# SWR_Tandem_Match.net
KiCad netlist of a schematic drawn in Altium Designer
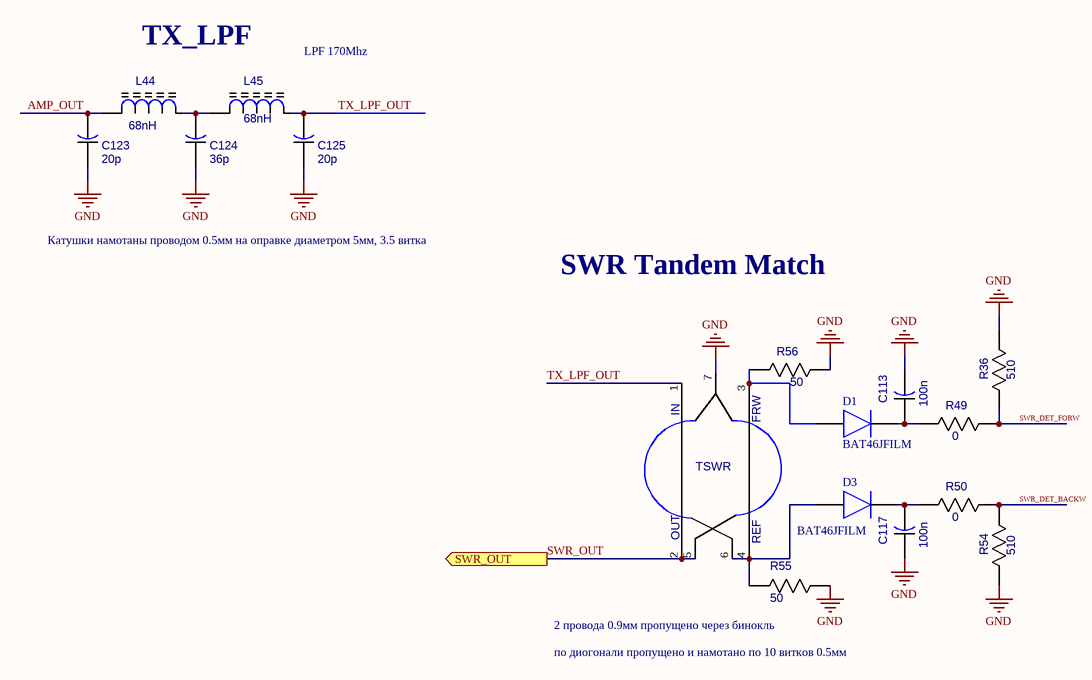
[diagram p0: SWR Tandem Match.SchDoc]

(export (version "E")
  (design (tool "Eeschema 10.0.6"))
  (components
    (comp (ref "C113")
      (value "100n")
      (footprint "CAP_0805")
      (description "CAP_0805")
      (libsource (lib "*") (part "CAP_0805"))
    )
    (comp (ref "C117")
      (value "100n")
      (footprint "CAP_0805")
      (description "CAP_0805")
      (libsource (lib "*") (part "CAP_0805"))
    )
    (comp (ref "C123")
      (value "20p")
      (footprint "CAP_1206")
      (description "CAP_1206")
      (libsource (lib "*") (part "CAP_1206"))
    )
    (comp (ref "C124")
      (value "36p")
      (footprint "CAP_1206")
      (description "CAP_1206")
      (libsource (lib "*") (part "CAP_1206"))
    )
    (comp (ref "C125")
      (value "20p")
      (footprint "CAP_1206")
      (description "CAP_1206")
      (libsource (lib "*") (part "CAP_1206"))
    )
    (comp (ref "D1")
      (value "BAT46JFILM")
      (footprint "SamacSys:SOD2513X117N")
      (description "Diode")
      (fields (field (name "MOUSER PART NUMBER") "511-BAT46JFILM") (field (name "RS PART NUMBER") "7146847P"))
      (libsource (lib "*") (part "BAT46JFILM"))
    )
    (comp (ref "D3")
      (value "BAT46JFILM")
      (footprint "SamacSys:SOD2513X117N")
      (description "Diode")
      (fields (field (name "MOUSER PART NUMBER") "511-BAT46JFILM") (field (name "RS PART NUMBER") "7146847P"))
      (libsource (lib "*") (part "BAT46JFILM"))
    )
    (comp (ref "L44")
      (value "68nH")
      (footprint "IND_FERRITE_CORE_1")
      (description "Inductor")
      (libsource (lib "*") (part "IND_FERRITE_CORE"))
    )
    (comp (ref "L45")
      (value "68nH")
      (footprint "IND_FERRITE_CORE_1")
      (description "Inductor")
      (libsource (lib "*") (part "IND_FERRITE_CORE"))
    )
    (comp (ref "R36")
      (value "510")
      (footprint "RES_0805")
      (description "RES_0805")
      (libsource (lib "*") (part "RES_0805"))
    )
    (comp (ref "R49")
      (value "0")
      (footprint "RES_0805")
      (description "RES_0805")
      (libsource (lib "*") (part "RES_0805"))
    )
    (comp (ref "R50")
      (value "0")
      (footprint "RES_0805")
      (description "RES_0805")
      (libsource (lib "*") (part "RES_0805"))
    )
    (comp (ref "R54")
      (value "510")
      (footprint "RES_0805")
      (description "RES_0805")
      (libsource (lib "*") (part "RES_0805"))
    )
    (comp (ref "R55")
      (value "50")
      (footprint "RES_1206")
      (description "RES_1206")
      (libsource (lib "*") (part "RES_1206"))
    )
    (comp (ref "R56")
      (value "50")
      (footprint "RES_1206")
      (description "RES_1206")
      (libsource (lib "*") (part "RES_1206"))
    )
    (comp (ref "TSWR")
      (value "SWR_TANDEM_MATCH")
      (footprint "SWR_TANDEM_MATCH")
      (libsource (lib "*") (part "SWR_TANDEM_MATCH"))
    )
  )
  (nets
    (net (code "1") (name "/AMP_OUT") (class "Default")
      (node (ref "C123") (pin "2") (pinfunction "2_2") (pintype "passive"))
      (node (ref "L44") (pin "1") (pinfunction "A_1") (pintype "passive"))
    )
    (net (code "2") (name "/SWR_DET_BACKW") (class "Default")
      (node (ref "R50") (pin "2") (pinfunction "2_2") (pintype "passive"))
      (node (ref "R54") (pin "2") (pinfunction "2_2") (pintype "passive"))
    )
    (net (code "3") (name "/SWR_DET_FORW") (class "Default")
      (node (ref "R36") (pin "1") (pinfunction "1_1") (pintype "passive"))
      (node (ref "R49") (pin "2") (pinfunction "2_2") (pintype "passive"))
    )
    (net (code "4") (name "/SWR_OUT") (class "Default")
      (node (ref "TSWR") (pin "2") (pinfunction "2_2") (pintype "passive"))
      (node (ref "TSWR") (pin "5") (pinfunction "5_5") (pintype "passive"))
    )
    (net (code "5") (name "/TX_LPF_OUT") (class "Default")
      (node (ref "C125") (pin "2") (pinfunction "2_2") (pintype "passive"))
      (node (ref "L45") (pin "2") (pinfunction "B_2") (pintype "passive"))
      (node (ref "TSWR") (pin "1") (pinfunction "1_1") (pintype "passive"))
    )
    (net (code "6") (name "GND") (class "Default")
      (node (ref "C113") (pin "2") (pinfunction "2_2") (pintype "passive"))
      (node (ref "C117") (pin "1") (pinfunction "1_1") (pintype "passive"))
      (node (ref "C123") (pin "1") (pinfunction "1_1") (pintype "passive"))
      (node (ref "C124") (pin "1") (pinfunction "1_1") (pintype "passive"))
      (node (ref "C125") (pin "1") (pinfunction "1_1") (pintype "passive"))
      (node (ref "R36") (pin "2") (pinfunction "2_2") (pintype "passive"))
      (node (ref "R54") (pin "1") (pinfunction "1_1") (pintype "passive"))
      (node (ref "R55") (pin "2") (pinfunction "2_2") (pintype "passive"))
      (node (ref "R56") (pin "2") (pinfunction "2_2") (pintype "passive"))
      (node (ref "TSWR") (pin "7") (pinfunction "7_7") (pintype "passive"))
    )
    (net (code "7") (name "Net-(D1-A)") (class "Default")
      (node (ref "D1") (pin "2") (pinfunction "A_2") (pintype "passive"))
      (node (ref "R56") (pin "1") (pinfunction "1_1") (pintype "passive"))
      (node (ref "TSWR") (pin "3") (pinfunction "3_3") (pintype "passive"))
    )
    (net (code "8") (name "Net-(D1-K)") (class "Default")
      (node (ref "C113") (pin "1") (pinfunction "1_1") (pintype "passive"))
      (node (ref "D1") (pin "1") (pinfunction "K_1") (pintype "passive"))
      (node (ref "R49") (pin "1") (pinfunction "1_1") (pintype "passive"))
    )
    (net (code "9") (name "Net-(D3-A)") (class "Default")
      (node (ref "D3") (pin "2") (pinfunction "A_2") (pintype "passive"))
      (node (ref "R55") (pin "1") (pinfunction "1_1") (pintype "passive"))
      (node (ref "TSWR") (pin "4") (pinfunction "4_4") (pintype "passive"))
      (node (ref "TSWR") (pin "6") (pinfunction "6_6") (pintype "passive"))
    )
    (net (code "10") (name "Net-(D3-K)") (class "Default")
      (node (ref "C117") (pin "2") (pinfunction "2_2") (pintype "passive"))
      (node (ref "D3") (pin "1") (pinfunction "K_1") (pintype "passive"))
      (node (ref "R50") (pin "1") (pinfunction "1_1") (pintype "passive"))
    )
    (net (code "11") (name "Net-(L44-B)") (class "Default")
      (node (ref "C124") (pin "2") (pinfunction "2_2") (pintype "passive"))
      (node (ref "L44") (pin "2") (pinfunction "B_2") (pintype "passive"))
      (node (ref "L45") (pin "1") (pinfunction "A_1") (pintype "passive"))
    )
  )
)
